# Vertical_Switching_Board.net
KiCad netlist of a schematic drawn in Altium Designer
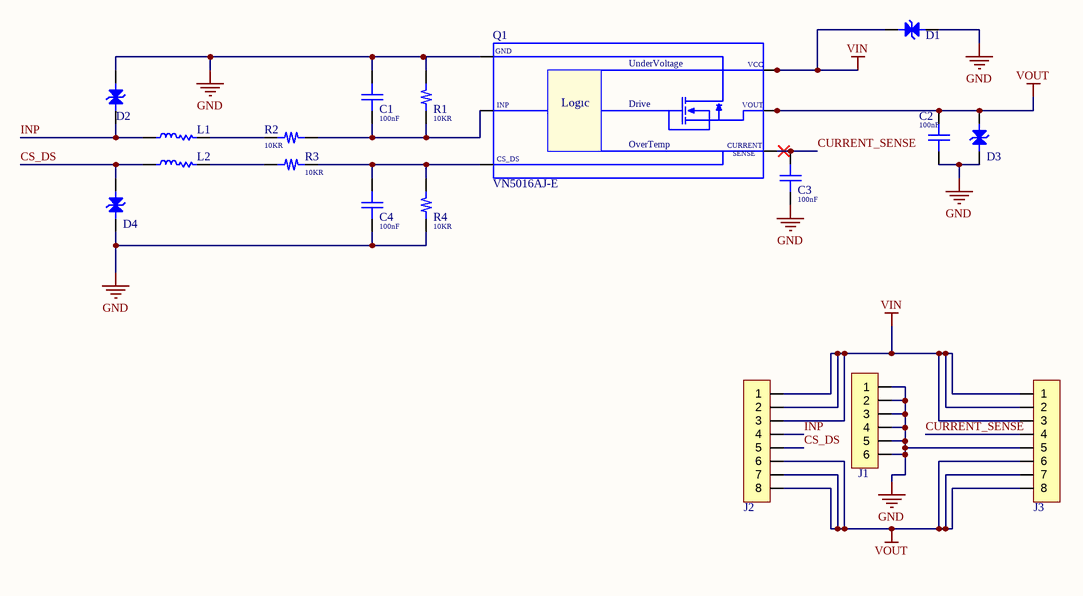
[diagram p0: Vertical Switching Board.SchDoc]

(export (version "E")
  (design (tool "Eeschema 10.0.6"))
  (components
    (comp (ref "C1")
      (value "100nF")
      (footprint "C-0603")
      (fields (field (name "Comment") "Cap-0603"))
      (libsource (lib "Vertical Switching Board") (part "Cap-0603"))
    )
    (comp (ref "C2")
      (value "100nF")
      (footprint "C-0603")
      (fields (field (name "Comment") "Cap-0603"))
      (libsource (lib "Vertical Switching Board") (part "Cap-0603"))
    )
    (comp (ref "C3")
      (value "100nF")
      (footprint "C-0603")
      (fields (field (name "Comment") "Cap-0603"))
      (libsource (lib "Vertical Switching Board") (part "Cap-0603"))
    )
    (comp (ref "C4")
      (value "100nF")
      (footprint "C-0603")
      (fields (field (name "Comment") "Cap-0603"))
      (libsource (lib "Vertical Switching Board") (part "Cap-0603"))
    )
    (comp (ref "D1")
      (value "TVS-Diode")
      (footprint "TVS")
      (libsource (lib "Vertical Switching Board") (part "TVS-Diode"))
    )
    (comp (ref "D2")
      (value "TVS-Diode")
      (footprint "TVS")
      (libsource (lib "Vertical Switching Board") (part "TVS-Diode"))
    )
    (comp (ref "D3")
      (value "TVS-Diode")
      (footprint "TVS")
      (libsource (lib "Vertical Switching Board") (part "TVS-Diode"))
    )
    (comp (ref "D4")
      (value "TVS-Diode")
      (footprint "TVS")
      (libsource (lib "Vertical Switching Board") (part "TVS-Diode"))
    )
    (comp (ref "J1")
      (value "Conn-6P")
      (footprint "6P-CONN")
      (libsource (lib "Vertical Switching Board") (part "Conn-6P"))
    )
    (comp (ref "J2")
      (value "Conn-8P")
      (footprint "8P-CONN")
      (libsource (lib "Vertical Switching Board") (part "Conn-8P"))
    )
    (comp (ref "J3") (value "Conn-8P") (footprint "8P-CONN") (libsource (lib "") (part "Conn-8P_1")))
    (comp (ref "L1")
      (value "Ferid-Bead")
      (footprint "FB-0603")
      (libsource (lib "Vertical Switching Board") (part "Ferid-Bead"))
    )
    (comp (ref "L2")
      (value "Ferid-Bead")
      (footprint "FB-0603")
      (libsource (lib "Vertical Switching Board") (part "Ferid-Bead"))
    )
    (comp (ref "Q1")
      (value "VN5016AJ-E")
      (footprint "PowerSSO-12")
      (libsource (lib "Vertical Switching Board") (part "VN5016AJ-E"))
    )
    (comp (ref "R1")
      (value "10KR")
      (footprint "R-0603")
      (fields (field (name "Comment") "Res-0603"))
      (libsource (lib "Vertical Switching Board") (part "Res-0603"))
    )
    (comp (ref "R2")
      (value "10KR")
      (footprint "R-0603")
      (fields (field (name "Comment") "Res-0603"))
      (libsource (lib "Vertical Switching Board") (part "Res-0603"))
    )
    (comp (ref "R3")
      (value "10KR")
      (footprint "R-0603")
      (fields (field (name "Comment") "Res-0603"))
      (libsource (lib "Vertical Switching Board") (part "Res-0603"))
    )
    (comp (ref "R4")
      (value "10KR")
      (footprint "R-0603")
      (fields (field (name "Comment") "Res-0603"))
      (libsource (lib "Vertical Switching Board") (part "Res-0603"))
    )
  )
  (nets
    (net (code "1") (name "/CS_DS") (class "Default")
      (node (ref "D4") (pin "2") (pinfunction "2_2") (pintype "passive"))
      (node (ref "J2") (pin "5") (pinfunction "5_5") (pintype "passive"))
      (node (ref "L2") (pin "1") (pinfunction "1_1") (pintype "passive"))
    )
    (net (code "2") (name "/CURRENT_SENSE") (class "Default")
      (node (ref "C3") (pin "2") (pinfunction "2_2") (pintype "passive"))
      (node (ref "J3") (pin "4") (pinfunction "4_4") (pintype "passive"))
      (node (ref "Q1") (pin "4") (pinfunction "CURRENT_SENSE_4") (pintype "passive"))
    )
    (net (code "3") (name "/INP") (class "Default")
      (node (ref "D2") (pin "1") (pinfunction "1_1") (pintype "passive"))
      (node (ref "J2") (pin "4") (pinfunction "4_4") (pintype "passive"))
      (node (ref "L1") (pin "1") (pinfunction "1_1") (pintype "passive"))
    )
    (net (code "4") (name "GND") (class "Default")
      (node (ref "C1") (pin "2") (pinfunction "2_2") (pintype "passive"))
      (node (ref "C2") (pin "1") (pinfunction "1_1") (pintype "passive"))
      (node (ref "C3") (pin "1") (pinfunction "1_1") (pintype "passive"))
      (node (ref "C4") (pin "1") (pinfunction "1_1") (pintype "passive"))
      (node (ref "D1") (pin "2") (pinfunction "2_2") (pintype "passive"))
      (node (ref "D2") (pin "2") (pinfunction "2_2") (pintype "passive"))
      (node (ref "D3") (pin "1") (pinfunction "1_1") (pintype "passive"))
      (node (ref "D4") (pin "1") (pinfunction "1_1") (pintype "passive"))
      (node (ref "J1") (pin "1") (pinfunction "1_1") (pintype "passive"))
      (node (ref "J1") (pin "2") (pinfunction "2_2") (pintype "passive"))
      (node (ref "J1") (pin "3") (pinfunction "3_3") (pintype "passive"))
      (node (ref "J1") (pin "4") (pinfunction "4_4") (pintype "passive"))
      (node (ref "J1") (pin "5") (pinfunction "5_5") (pintype "passive"))
      (node (ref "J1") (pin "6") (pinfunction "6_6") (pintype "passive"))
      (node (ref "J3") (pin "5") (pinfunction "5_5") (pintype "passive"))
      (node (ref "Q1") (pin "2") (pinfunction "GND_2") (pintype "passive"))
      (node (ref "R1") (pin "2") (pinfunction "2_2") (pintype "passive"))
      (node (ref "R4") (pin "1") (pinfunction "1_1") (pintype "passive"))
    )
    (net (code "5") (name "Net-(L1-Pad2)") (class "Default")
      (node (ref "L1") (pin "2") (pinfunction "2_2") (pintype "passive"))
      (node (ref "R2") (pin "1") (pinfunction "1_1") (pintype "passive"))
    )
    (net (code "6") (name "Net-(L2-Pad2)") (class "Default")
      (node (ref "L2") (pin "2") (pinfunction "2_2") (pintype "passive"))
      (node (ref "R3") (pin "1") (pinfunction "1_1") (pintype "passive"))
    )
    (net (code "7") (name "Net-(Q1-CS_DC)") (class "Default")
      (node (ref "C4") (pin "2") (pinfunction "2_2") (pintype "passive"))
      (node (ref "Q1") (pin "5") (pinfunction "CS_DC_5") (pintype "passive"))
      (node (ref "R3") (pin "2") (pinfunction "2_2") (pintype "passive"))
      (node (ref "R4") (pin "2") (pinfunction "2_2") (pintype "passive"))
    )
    (net (code "8") (name "Net-(Q1-INP)") (class "Default")
      (node (ref "C1") (pin "1") (pinfunction "1_1") (pintype "passive"))
      (node (ref "Q1") (pin "3") (pinfunction "INP_3") (pintype "passive"))
      (node (ref "R1") (pin "1") (pinfunction "1_1") (pintype "passive"))
      (node (ref "R2") (pin "2") (pinfunction "2_2") (pintype "passive"))
    )
    (net (code "9") (name "VIN") (class "Default")
      (node (ref "D1") (pin "1") (pinfunction "1_1") (pintype "passive"))
      (node (ref "J2") (pin "1") (pinfunction "1_1") (pintype "passive"))
      (node (ref "J2") (pin "2") (pinfunction "2_2") (pintype "passive"))
      (node (ref "J2") (pin "3") (pinfunction "3_3") (pintype "passive"))
      (node (ref "J3") (pin "1") (pinfunction "1_1") (pintype "passive"))
      (node (ref "J3") (pin "2") (pinfunction "2_2") (pintype "passive"))
      (node (ref "J3") (pin "3") (pinfunction "3_3") (pintype "passive"))
      (node (ref "Q1") (pin "1") (pinfunction "VCC_1") (pintype "passive"))
      (node (ref "Q1") (pin "6") (pinfunction "VCC_6") (pintype "passive"))
    )
    (net (code "10") (name "VOUT") (class "Default")
      (node (ref "C2") (pin "2") (pinfunction "2_2") (pintype "passive"))
      (node (ref "D3") (pin "2") (pinfunction "2_2") (pintype "passive"))
      (node (ref "J2") (pin "6") (pinfunction "6_6") (pintype "passive"))
      (node (ref "J2") (pin "7") (pinfunction "7_7") (pintype "passive"))
      (node (ref "J2") (pin "8") (pinfunction "8_8") (pintype "passive"))
      (node (ref "J3") (pin "6") (pinfunction "6_6") (pintype "passive"))
      (node (ref "J3") (pin "7") (pinfunction "7_7") (pintype "passive"))
      (node (ref "J3") (pin "8") (pinfunction "8_8") (pintype "passive"))
      (node (ref "Q1") (pin "10") (pinfunction "OUT_10") (pintype "passive"))
      (node (ref "Q1") (pin "11") (pinfunction "OUT_11") (pintype "passive"))
      (node (ref "Q1") (pin "12") (pinfunction "OUT_12") (pintype "passive"))
      (node (ref "Q1") (pin "7") (pinfunction "OUT_7") (pintype "passive"))
      (node (ref "Q1") (pin "8") (pinfunction "OUT_8") (pintype "passive"))
      (node (ref "Q1") (pin "9") (pinfunction "OUT_9") (pintype "passive"))
    )
  )
)
